# BMP280_board.net
KiCad netlist of a schematic drawn in EAGLE
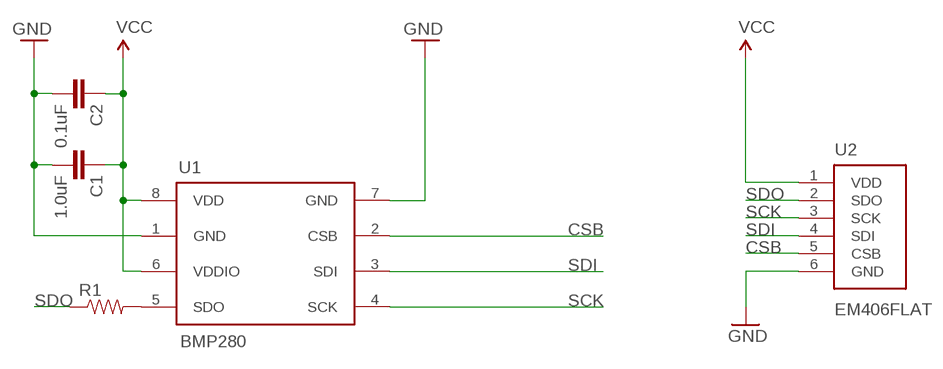
[diagram p0: schematic, sheet 1]

(export (version "E")
  (design (tool "Eeschema 10.0.6"))
  (components
    (comp (ref "C1")
      (value "1.0uF")
      (footprint "eagle-import:0603-CAP")
      (libsource (lib "eagle-import") (part "0.1UF-25V(+80/-20%)(0603)"))
    )
    (comp (ref "C2")
      (value "0.1uF")
      (footprint "eagle-import:0603-CAP")
      (libsource (lib "eagle-import") (part "0.1UF-25V(+80/-20%)(0603)"))
    )
    (comp (ref "R1")
      (value "RESISTOR0603-RES")
      (footprint "eagle-import:0603-RES")
      (libsource (lib "eagle-import") (part "RESISTOR0603-RES"))
    )
    (comp (ref "U1")
      (value "BMP280")
      (footprint "eagle-import:LGA-8")
      (libsource (lib "eagle-import") (part "BMP280_PITCH0.65"))
    )
    (comp (ref "U2")
      (value "EM406FLAT")
      (footprint "eagle-import:EM406-FLAT")
      (libsource (lib "eagle-import") (part "EM406FLAT"))
    )
  )
  (nets
    (net (code "1") (name "/CSB") (class "Default")
      (node (ref "U1") (pin "2") (pinfunction "CSB_2") (pintype "bidirectional"))
      (node (ref "U2") (pin "5") (pinfunction "CSB_5") (pintype "bidirectional"))
    )
    (net (code "2") (name "/SCK") (class "Default")
      (node (ref "U1") (pin "4") (pinfunction "SCK_4") (pintype "bidirectional"))
      (node (ref "U2") (pin "3") (pinfunction "SCK_3") (pintype "bidirectional"))
    )
    (net (code "3") (name "/SDI") (class "Default")
      (node (ref "U1") (pin "3") (pinfunction "SDI_3") (pintype "bidirectional"))
      (node (ref "U2") (pin "4") (pinfunction "SDI_4") (pintype "bidirectional"))
    )
    (net (code "4") (name "/SDO") (class "Default")
      (node (ref "R1") (pin "1") (pinfunction "1_1") (pintype "passive"))
      (node (ref "U2") (pin "2") (pinfunction "SDO_2") (pintype "bidirectional"))
    )
    (net (code "5") (name "GND") (class "Default")
      (node (ref "C1") (pin "2") (pinfunction "2_2") (pintype "passive"))
      (node (ref "C2") (pin "2") (pinfunction "2_2") (pintype "passive"))
      (node (ref "U1") (pin "1") (pinfunction "GND_1") (pintype "bidirectional"))
      (node (ref "U1") (pin "7") (pinfunction "GND_7") (pintype "bidirectional"))
      (node (ref "U2") (pin "6") (pinfunction "GND_6") (pintype "bidirectional"))
    )
    (net (code "6") (name "Net-(U1-SDO)") (class "Default")
      (node (ref "R1") (pin "2") (pinfunction "2_2") (pintype "passive"))
      (node (ref "U1") (pin "5") (pinfunction "SDO_5") (pintype "bidirectional"))
    )
    (net (code "7") (name "VCC") (class "Default")
      (node (ref "C1") (pin "1") (pinfunction "1_1") (pintype "passive"))
      (node (ref "C2") (pin "1") (pinfunction "1_1") (pintype "passive"))
      (node (ref "U1") (pin "6") (pinfunction "VDDIO_6") (pintype "bidirectional"))
      (node (ref "U1") (pin "8") (pinfunction "VDD_8") (pintype "bidirectional"))
      (node (ref "U2") (pin "1") (pinfunction "VDD_1") (pintype "bidirectional"))
    )
  )
)
